# RS-485_SN65HVD72DRBR.net
KiCad netlist of a schematic drawn in Altium Designer
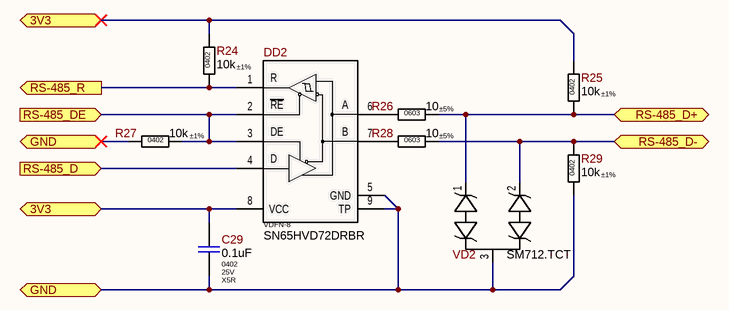
[diagram p0: RS-485_SN65HVD72DRBR.SchDoc]

(export (version "E")
  (design (tool "Eeschema 10.0.6"))
  (components
    (comp (ref "C29")
      (value "0.1uF")
      (footprint "C_CERAMIC_0402_MED")
      (description "100nF 25V X5R ±10% 0402 Ceramic Capacitor RoHS")
      (fields
        (field (name "PACKAGE") "0402")
        (field (name "VOLTAGE") "25V")
        (field (name "DIELECTRIC TYPE") "X5R")
        (field (name "PART NUMBER") "CL05A104KA5NNNC")
        (field (name "MANUFACTURER") "Samsung Electro-Mechanics")
      )
      (libsource (lib "EL.XXX.T01") (part "Capacitor-NonPolar"))
    )
    (comp (ref "DD2")
      (value "SN65HVD72DRBR")
      (footprint "TI-SON8-65P300X100_HS")
      (description "3.3V 1/1 Transceiver Half RS422 Up to 250 kbps, RS485 With IEC ESD protection, SON-8")
      (fields
        (field (name "PACKAGE") "VDFN-8")
        (field (name "PART NUMBER") "SN65HVD72DRBR")
        (field (name "MANUFACTURER") "Texas Instruments")
      )
      (libsource (lib "EL.XXX.T01") (part "SN65HVD7xDRB"))
    )
    (comp (ref "R24")
      (value "10k")
      (footprint "R_ANY_CHIP_0402_MED")
      (description "10 kOhms ±1% 1/16W 0402 Thick Film Resistor")
      (fields
        (field (name "TOLERANCE") "±1%")
        (field (name "PACKAGE") "0402")
        (field (name "PART NUMBER") "RC0402FR-0710KL")
        (field (name "MANUFACTURER") "Yageo")
      )
      (libsource (lib "EL.XXX.T01") (part "Resistor"))
    )
    (comp (ref "R25")
      (value "10k")
      (footprint "R_ANY_CHIP_0402_MED")
      (description "10 kOhms ±1% 1/16W 0402 Thick Film Resistor")
      (fields
        (field (name "TOLERANCE") "±1%")
        (field (name "PACKAGE") "0402")
        (field (name "PART NUMBER") "RC0402FR-0710KL")
        (field (name "MANUFACTURER") "Yageo")
      )
      (libsource (lib "EL.XXX.T01") (part "Resistor"))
    )
    (comp (ref "R26")
      (value "10")
      (footprint "R_ANY_CHIP_0603_MED")
      (description "10 Ohms ±5%, 1/10W 0603 Thick Film Resistor")
      (fields
        (field (name "TOLERANCE") "±5%")
        (field (name "PACKAGE") "0603")
        (field (name "PART NUMBER") "RC0603JR-0710RL")
        (field (name "MANUFACTURER") "Yageo")
      )
      (libsource (lib "EL.XXX.T01") (part "Resistor"))
    )
    (comp (ref "R27")
      (value "10k")
      (footprint "R_ANY_CHIP_0402_MED")
      (description "10 kOhms ±1% 1/16W 0402 Thick Film Resistor")
      (fields
        (field (name "TOLERANCE") "±1%")
        (field (name "PACKAGE") "0402")
        (field (name "PART NUMBER") "RC0402FR-0710KL")
        (field (name "MANUFACTURER") "Yageo")
      )
      (libsource (lib "EL.XXX.T01") (part "Resistor"))
    )
    (comp (ref "R28")
      (value "10")
      (footprint "R_ANY_CHIP_0603_MED")
      (description "10 Ohms ±5%, 1/10W 0603 Thick Film Resistor")
      (fields
        (field (name "TOLERANCE") "±5%")
        (field (name "PACKAGE") "0603")
        (field (name "PART NUMBER") "RC0603JR-0710RL")
        (field (name "MANUFACTURER") "Yageo")
      )
      (libsource (lib "EL.XXX.T01") (part "Resistor"))
    )
    (comp (ref "R29")
      (value "10k")
      (footprint "R_ANY_CHIP_0402_MED")
      (description "10 kOhms ±1% 1/16W 0402 Thick Film Resistor")
      (fields
        (field (name "TOLERANCE") "±1%")
        (field (name "PACKAGE") "0402")
        (field (name "PART NUMBER") "RC0402FR-0710KL")
        (field (name "MANUFACTURER") "Yageo")
      )
      (libsource (lib "EL.XXX.T01") (part "Resistor"))
    )
    (comp (ref "VD2")
      (value "SM712.TCT")
      (footprint "SOT-23_MED")
      (description "TVS Diode 26V and 19V Clamp, 21A and 38A (8/20us) Ipp, SOT-23")
      (fields
        (field (name "PART NUMBER") "SM712.TCT")
        (field (name "MANUFACTURER") "Semtech")
        (field (name "VOLTAGE") "13.3V, 7.5V")
      )
      (libsource (lib "EL.XXX.T01") (part "SM712.TCT"))
    )
  )
  (nets
    (net (code "1") (name "/3V3") (class "Default")
      (node (ref "C29") (pin "1") (pinfunction "1_1") (pintype "passive"))
      (node (ref "DD2") (pin "8") (pinfunction "VCC_8") (pintype "passive"))
      (node (ref "R24") (pin "1") (pintype "passive"))
      (node (ref "R25") (pin "1") (pintype "passive"))
    )
    (net (code "2") (name "/GND") (class "Default")
      (node (ref "C29") (pin "2") (pinfunction "2_2") (pintype "passive"))
      (node (ref "DD2") (pin "5") (pinfunction "GND_5") (pintype "passive"))
      (node (ref "DD2") (pin "9") (pinfunction "TP_9") (pintype "passive"))
      (node (ref "R27") (pin "2") (pintype "passive"))
      (node (ref "R29") (pin "2") (pintype "passive"))
      (node (ref "VD2") (pin "3") (pintype "passive"))
    )
    (net (code "3") (name "/RS-485_D") (class "Default")
      (node (ref "DD2") (pin "4") (pinfunction "DI_4") (pintype "passive"))
    )
    (net (code "4") (name "/RS-485_D+") (class "Default")
      (node (ref "R25") (pin "2") (pintype "passive"))
      (node (ref "R26") (pin "2") (pintype "passive"))
      (node (ref "VD2") (pin "1") (pintype "passive"))
    )
    (net (code "5") (name "/RS-485_D-") (class "Default")
      (node (ref "R28") (pin "2") (pintype "passive"))
      (node (ref "R29") (pin "1") (pintype "passive"))
      (node (ref "VD2") (pin "2") (pintype "passive"))
    )
    (net (code "6") (name "/RS-485_DE") (class "Default")
      (node (ref "DD2") (pin "2") (pinfunction "~{RE}_2") (pintype "passive"))
      (node (ref "DD2") (pin "3") (pinfunction "DE_3") (pintype "passive"))
      (node (ref "R27") (pin "1") (pintype "passive"))
    )
    (net (code "7") (name "/RS-485_R") (class "Default")
      (node (ref "DD2") (pin "1") (pinfunction "RO_1") (pintype "passive"))
      (node (ref "R24") (pin "2") (pintype "passive"))
    )
    (net (code "8") (name "Net-(DD2-A)") (class "Default")
      (node (ref "DD2") (pin "6") (pinfunction "A_6") (pintype "passive"))
      (node (ref "R26") (pin "1") (pintype "passive"))
    )
    (net (code "9") (name "Net-(DD2-B)") (class "Default")
      (node (ref "DD2") (pin "7") (pinfunction "B_7") (pintype "passive"))
      (node (ref "R28") (pin "1") (pintype "passive"))
    )
  )
)
